# Schematic.net
KiCad netlist of a schematic drawn in EAGLE
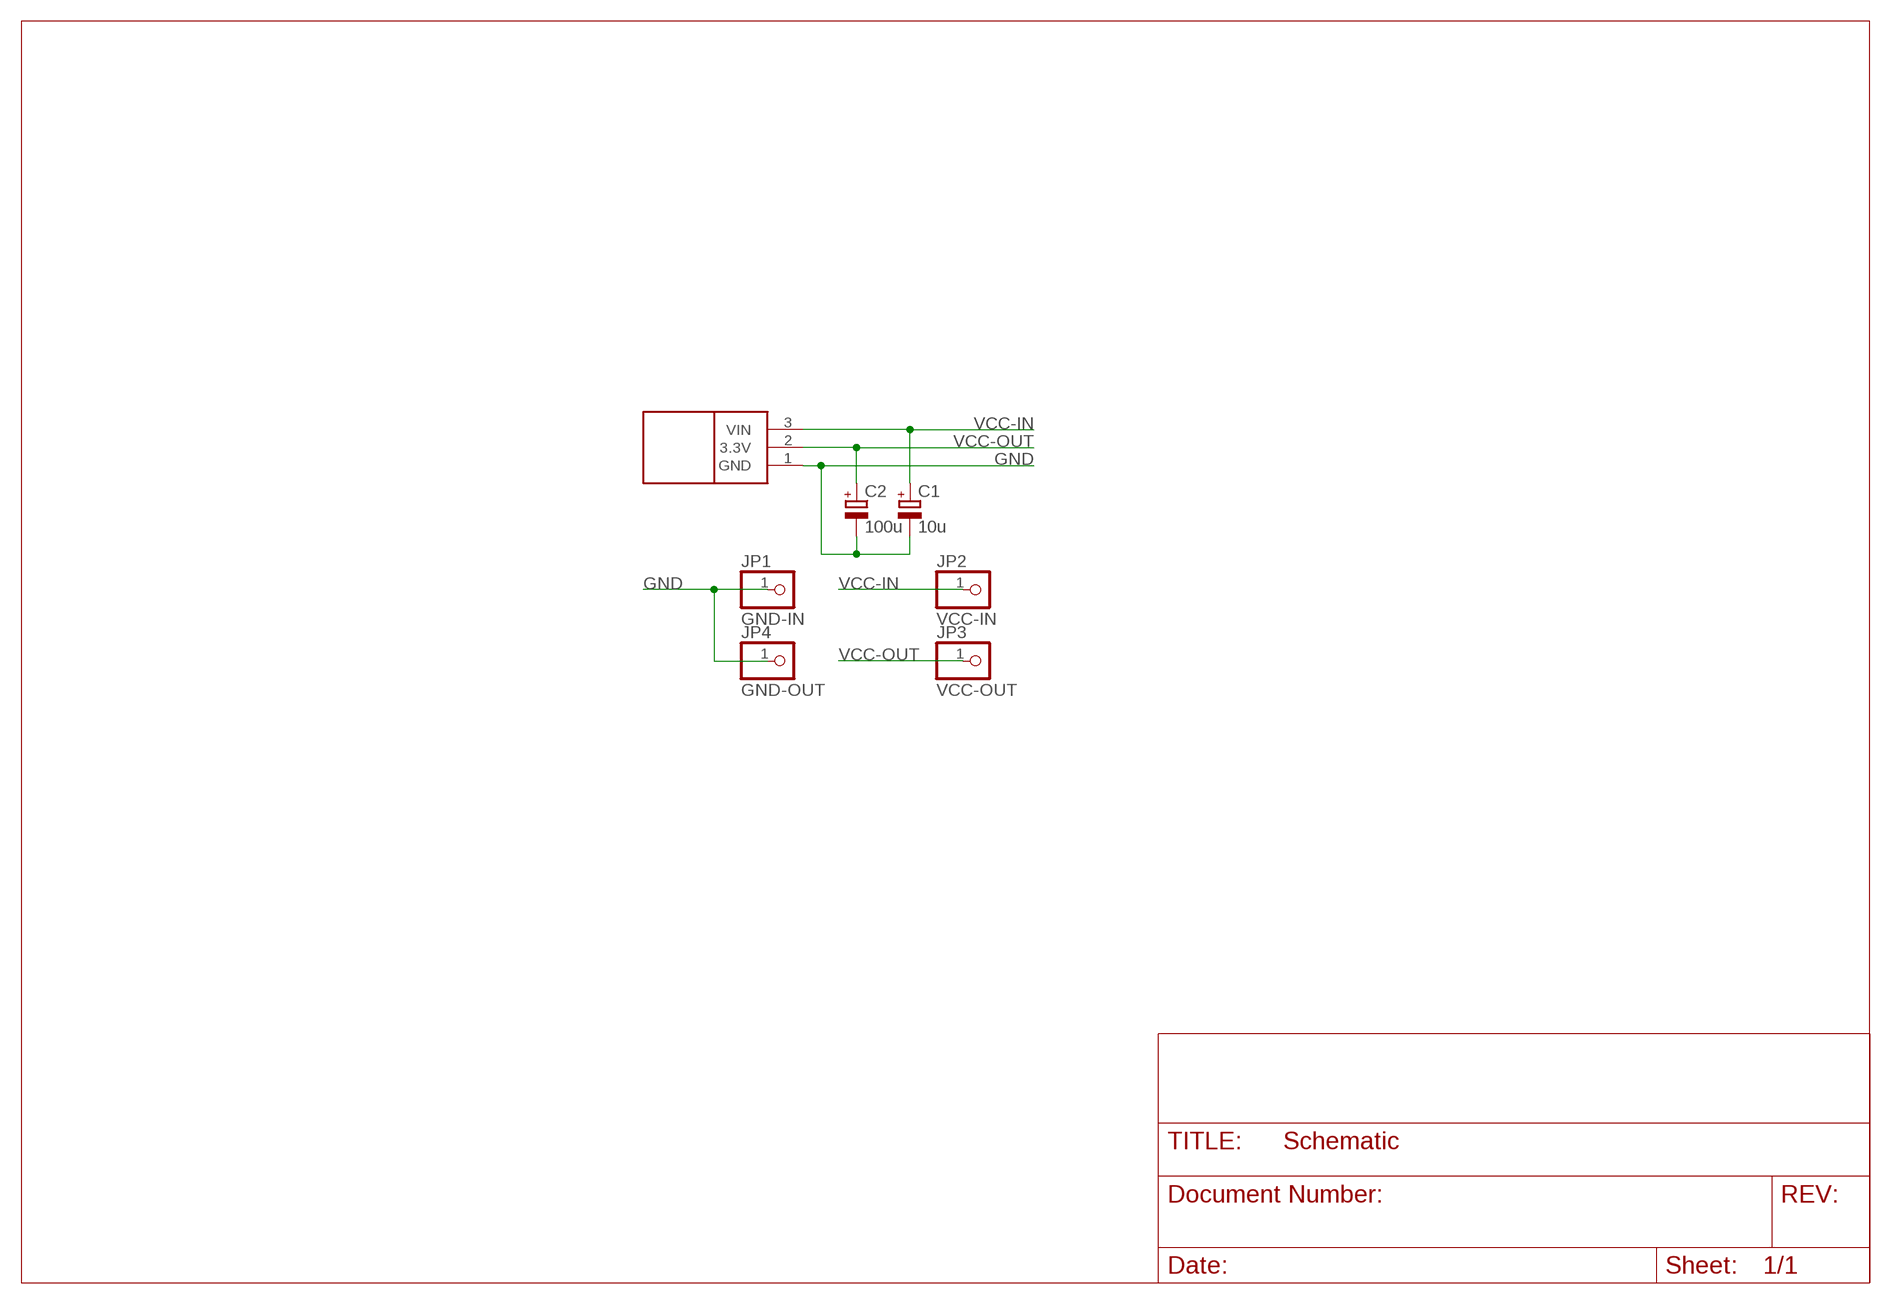
[diagram p0: schematic, sheet 1]

(export (version "E")
  (design (tool "Eeschema 10.0.6"))
  (components
    (comp (ref "C1")
      (value "10u")
      (footprint "eagle-import:E2,5-7")
      (libsource (lib "eagle-import") (part "CPOL-EUE2.5-7"))
    )
    (comp (ref "C2")
      (value "100u")
      (footprint "eagle-import:E3,5-8")
      (libsource (lib "eagle-import") (part "CPOL-EUE3.5-8"))
    )
    (comp (ref "JP1")
      (value "GND-IN")
      (footprint "eagle-import:1X01")
      (libsource (lib "eagle-import") (part "PINHD-1X1"))
    )
    (comp (ref "JP2")
      (value "VCC-IN")
      (footprint "eagle-import:1X01")
      (libsource (lib "eagle-import") (part "PINHD-1X1"))
    )
    (comp (ref "JP3")
      (value "VCC-OUT")
      (footprint "eagle-import:1X01")
      (libsource (lib "eagle-import") (part "PINHD-1X1"))
    )
    (comp (ref "JP4")
      (value "GND-OUT")
      (footprint "eagle-import:1X01")
      (libsource (lib "eagle-import") (part "PINHD-1X1"))
    )
    (comp (ref "U$1")
      (value "LD33VHORIZONTAL")
      (footprint "eagle-import:TO220")
      (libsource (lib "eagle-import") (part "LD33VHORIZONTAL"))
    )
  )
  (nets
    (net (code "1") (name "/GND") (class "Default")
      (node (ref "C1") (pin "-") (pinfunction "-_-") (pintype "passive"))
      (node (ref "C2") (pin "-") (pinfunction "-_-") (pintype "passive"))
      (node (ref "JP1") (pin "1") (pinfunction "1_1") (pintype "passive"))
      (node (ref "JP4") (pin "1") (pinfunction "1_1") (pintype "passive"))
      (node (ref "U$1") (pin "1") (pinfunction "GND_1") (pintype "bidirectional"))
    )
    (net (code "2") (name "/VCC-IN") (class "Default")
      (node (ref "C1") (pin "+") (pinfunction "+_+") (pintype "passive"))
      (node (ref "JP2") (pin "1") (pinfunction "1_1") (pintype "passive"))
      (node (ref "U$1") (pin "3") (pinfunction "VIN_3") (pintype "bidirectional"))
    )
    (net (code "3") (name "/VCC-OUT") (class "Default")
      (node (ref "C2") (pin "+") (pinfunction "+_+") (pintype "passive"))
      (node (ref "JP3") (pin "1") (pinfunction "1_1") (pintype "passive"))
      (node (ref "U$1") (pin "2") (pinfunction "3.3V_2") (pintype "bidirectional"))
    )
  )
)
